# moodlight.net
KiCad netlist of a schematic drawn in EAGLE
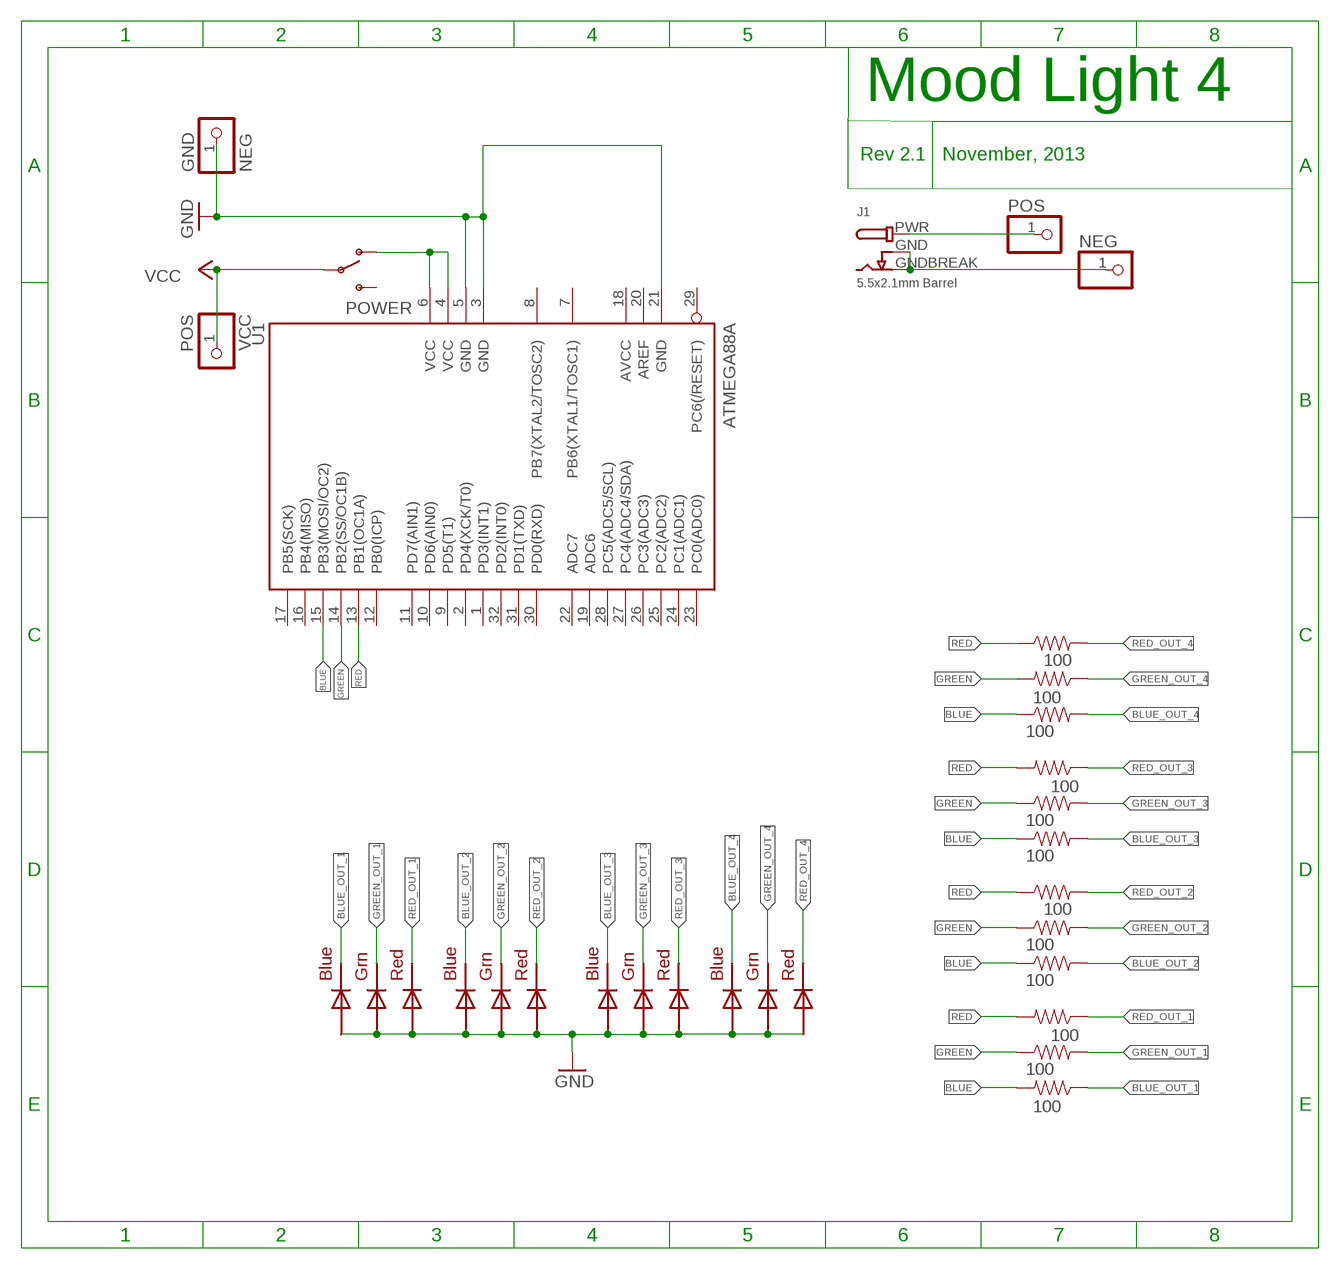
[diagram p0: schematic, sheet 1]

(export (version "E")
  (design (tool "Eeschema 10.0.6"))
  (components
    (comp (ref "GND")
      (value "NEG")
      (footprint "eagle-import:1X01")
      (libsource (lib "eagle-import") (part "PINHD-1X1"))
    )
    (comp (ref "J1")
      (value "5.5x2.1mm Barrel")
      (footprint "eagle-import:DCJACK_2MM_SMT")
      (libsource (lib "eagle-import") (part "DCBARRELSMT"))
    )
    (comp (ref "LED1")
      (value "RGBLED5050")
      (footprint "eagle-import:RGBLED5050")
      (libsource (lib "eagle-import") (part "RGBLED5050"))
    )
    (comp (ref "LED2")
      (value "RGBLED5050")
      (footprint "eagle-import:RGBLED5050")
      (libsource (lib "eagle-import") (part "RGBLED5050"))
    )
    (comp (ref "LED3")
      (value "RGBLED5050")
      (footprint "eagle-import:RGBLED5050")
      (libsource (lib "eagle-import") (part "RGBLED5050"))
    )
    (comp (ref "LED4")
      (value "RGBLED5050")
      (footprint "eagle-import:RGBLED5050")
      (libsource (lib "eagle-import") (part "RGBLED5050"))
    )
    (comp (ref "NEG")
      (value "PINHD-1X1")
      (footprint "eagle-import:1X01")
      (libsource (lib "eagle-import") (part "PINHD-1X1"))
    )
    (comp (ref "POS")
      (value "PINHD-1X1")
      (footprint "eagle-import:1X01")
      (libsource (lib "eagle-import") (part "PINHD-1X1"))
    )
    (comp (ref "POWER")
      (value "5V")
      (footprint "eagle-import:SWITCH-SPDT")
      (libsource (lib "eagle-import") (part "SWITCH-SPDTPTH"))
    )
    (comp (ref "R1")
      (value "100")
      (footprint "eagle-import:0603-RES")
      (libsource (lib "eagle-import") (part "220-5%"))
    )
    (comp (ref "R2")
      (value "100")
      (footprint "eagle-import:0603-RES")
      (libsource (lib "eagle-import") (part "220-5%"))
    )
    (comp (ref "R3")
      (value "100")
      (footprint "eagle-import:0603-RES")
      (libsource (lib "eagle-import") (part "220-5%"))
    )
    (comp (ref "R4")
      (value "100")
      (footprint "eagle-import:0603-RES")
      (libsource (lib "eagle-import") (part "220-5%"))
    )
    (comp (ref "R5")
      (value "100")
      (footprint "eagle-import:0603-RES")
      (libsource (lib "eagle-import") (part "220-5%"))
    )
    (comp (ref "R6")
      (value "100")
      (footprint "eagle-import:0603-RES")
      (libsource (lib "eagle-import") (part "220-5%"))
    )
    (comp (ref "R7")
      (value "100")
      (footprint "eagle-import:0603-RES")
      (libsource (lib "eagle-import") (part "220-5%"))
    )
    (comp (ref "R8")
      (value "100")
      (footprint "eagle-import:0603-RES")
      (libsource (lib "eagle-import") (part "220-5%"))
    )
    (comp (ref "R9")
      (value "100")
      (footprint "eagle-import:0603-RES")
      (libsource (lib "eagle-import") (part "220-5%"))
    )
    (comp (ref "R10")
      (value "100")
      (footprint "eagle-import:0603-RES")
      (libsource (lib "eagle-import") (part "220-5%"))
    )
    (comp (ref "R11")
      (value "100")
      (footprint "eagle-import:0603-RES")
      (libsource (lib "eagle-import") (part "220-5%"))
    )
    (comp (ref "R12")
      (value "100")
      (footprint "eagle-import:0603-RES")
      (libsource (lib "eagle-import") (part "220-5%"))
    )
    (comp (ref "U1")
      (value "ATMEGA88A")
      (footprint "eagle-import:TQFP32-08")
      (fields (field (name "MPN") "ATMEGA8-16AU"))
      (libsource (lib "eagle-import") (part "MEGA8-AI"))
    )
    (comp (ref "VCC")
      (value "POS")
      (footprint "eagle-import:1X01")
      (libsource (lib "eagle-import") (part "PINHD-1X1"))
    )
  )
  (nets
    (net (code "1") (name "/AVCC") (class "Default")
      (node (ref "U1") (pin "18") (pinfunction "AVCC_18") (pintype "power_in"))
    )
    (net (code "2") (name "BLUE") (class "Default")
      (node (ref "R12") (pin "2") (pinfunction "2_2") (pintype "passive"))
      (node (ref "R3") (pin "1") (pinfunction "1_1") (pintype "passive"))
      (node (ref "R6") (pin "1") (pinfunction "1_1") (pintype "passive"))
      (node (ref "R9") (pin "1") (pinfunction "1_1") (pintype "passive"))
      (node (ref "U1") (pin "15") (pinfunction "PB3(MOSI/OC2)_15") (pintype "bidirectional"))
    )
    (net (code "3") (name "BLUE_OUT_1") (class "Default")
      (node (ref "LED1") (pin "4") (pinfunction "BLUE_C_4") (pintype "bidirectional"))
      (node (ref "R12") (pin "1") (pinfunction "1_1") (pintype "passive"))
    )
    (net (code "4") (name "BLUE_OUT_2") (class "Default")
      (node (ref "LED2") (pin "4") (pinfunction "BLUE_C_4") (pintype "bidirectional"))
      (node (ref "R9") (pin "2") (pinfunction "2_2") (pintype "passive"))
    )
    (net (code "5") (name "BLUE_OUT_3") (class "Default")
      (node (ref "LED3") (pin "4") (pinfunction "BLUE_C_4") (pintype "bidirectional"))
      (node (ref "R6") (pin "2") (pinfunction "2_2") (pintype "passive"))
    )
    (net (code "6") (name "BLUE_OUT_4") (class "Default")
      (node (ref "LED4") (pin "4") (pinfunction "BLUE_C_4") (pintype "bidirectional"))
      (node (ref "R3") (pin "2") (pinfunction "2_2") (pintype "passive"))
    )
    (net (code "7") (name "GND") (class "Default")
      (node (ref "GND") (pin "1") (pinfunction "1_1") (pintype "passive"))
      (node (ref "LED1") (pin "1") (pinfunction "GREEN_A_1") (pintype "bidirectional"))
      (node (ref "LED1") (pin "2") (pinfunction "RED_A_2") (pintype "bidirectional"))
      (node (ref "LED1") (pin "3") (pinfunction "BLUE_A_3") (pintype "bidirectional"))
      (node (ref "LED2") (pin "1") (pinfunction "GREEN_A_1") (pintype "bidirectional"))
      (node (ref "LED2") (pin "2") (pinfunction "RED_A_2") (pintype "bidirectional"))
      (node (ref "LED2") (pin "3") (pinfunction "BLUE_A_3") (pintype "bidirectional"))
      (node (ref "LED3") (pin "1") (pinfunction "GREEN_A_1") (pintype "bidirectional"))
      (node (ref "LED3") (pin "2") (pinfunction "RED_A_2") (pintype "bidirectional"))
      (node (ref "LED3") (pin "3") (pinfunction "BLUE_A_3") (pintype "bidirectional"))
      (node (ref "LED4") (pin "1") (pinfunction "GREEN_A_1") (pintype "bidirectional"))
      (node (ref "LED4") (pin "2") (pinfunction "RED_A_2") (pintype "bidirectional"))
      (node (ref "LED4") (pin "3") (pinfunction "BLUE_A_3") (pintype "bidirectional"))
      (node (ref "U1") (pin "21") (pinfunction "GND_21") (pintype "power_in"))
      (node (ref "U1") (pin "3") (pinfunction "GND_3") (pintype "power_in"))
      (node (ref "U1") (pin "5") (pinfunction "GND_5") (pintype "power_in"))
    )
    (net (code "8") (name "GREEN") (class "Default")
      (node (ref "R11") (pin "1") (pinfunction "1_1") (pintype "passive"))
      (node (ref "R2") (pin "2") (pinfunction "2_2") (pintype "passive"))
      (node (ref "R5") (pin "1") (pinfunction "1_1") (pintype "passive"))
      (node (ref "R8") (pin "1") (pinfunction "1_1") (pintype "passive"))
      (node (ref "U1") (pin "14") (pinfunction "PB2(SS/OC1B)_14") (pintype "bidirectional"))
    )
    (net (code "9") (name "GREEN_OUT_1") (class "Default")
      (node (ref "LED1") (pin "6") (pinfunction "GREEN_C_6") (pintype "bidirectional"))
      (node (ref "R11") (pin "2") (pinfunction "2_2") (pintype "passive"))
    )
    (net (code "10") (name "GREEN_OUT_2") (class "Default")
      (node (ref "LED2") (pin "6") (pinfunction "GREEN_C_6") (pintype "bidirectional"))
      (node (ref "R8") (pin "2") (pinfunction "2_2") (pintype "passive"))
    )
    (net (code "11") (name "GREEN_OUT_3") (class "Default")
      (node (ref "LED3") (pin "6") (pinfunction "GREEN_C_6") (pintype "bidirectional"))
      (node (ref "R5") (pin "2") (pinfunction "2_2") (pintype "passive"))
    )
    (net (code "12") (name "GREEN_OUT_4") (class "Default")
      (node (ref "LED4") (pin "6") (pinfunction "GREEN_C_6") (pintype "bidirectional"))
      (node (ref "R2") (pin "1") (pinfunction "1_1") (pintype "passive"))
    )
    (net (code "13") (name "Net-(J1-GND)") (class "Default")
      (node (ref "J1") (pin "GND") (pinfunction "GNDBREAK_GND") (pintype "power_in"))
      (node (ref "J1") (pin "GNDBREAK") (pinfunction "GND_GNDBREAK") (pintype "power_in"))
      (node (ref "NEG") (pin "1") (pinfunction "1_1") (pintype "passive"))
    )
    (net (code "14") (name "Net-(J1-PadPWR)") (class "Default")
      (node (ref "J1") (pin "PWR") (pinfunction "PWR_PWR") (pintype "power_in"))
      (node (ref "POS") (pin "1") (pinfunction "1_1") (pintype "passive"))
    )
    (net (code "15") (name "Net-(POWER-O)") (class "Default")
      (node (ref "POWER") (pin "1") (pinfunction "O_1") (pintype "passive"))
      (node (ref "U1") (pin "4") (pinfunction "VCC_4") (pintype "power_in"))
      (node (ref "U1") (pin "6") (pinfunction "VCC_6") (pintype "power_in"))
    )
    (net (code "16") (name "RED") (class "Default")
      (node (ref "R1") (pin "1") (pinfunction "1_1") (pintype "passive"))
      (node (ref "R10") (pin "2") (pinfunction "2_2") (pintype "passive"))
      (node (ref "R4") (pin "2") (pinfunction "2_2") (pintype "passive"))
      (node (ref "R7") (pin "1") (pinfunction "1_1") (pintype "passive"))
      (node (ref "U1") (pin "13") (pinfunction "PB1(OC1A)_13") (pintype "bidirectional"))
    )
    (net (code "17") (name "RED_OUT_1") (class "Default")
      (node (ref "LED1") (pin "5") (pinfunction "RED_C_5") (pintype "bidirectional"))
      (node (ref "R10") (pin "1") (pinfunction "1_1") (pintype "passive"))
    )
    (net (code "18") (name "RED_OUT_2") (class "Default")
      (node (ref "LED2") (pin "5") (pinfunction "RED_C_5") (pintype "bidirectional"))
      (node (ref "R7") (pin "2") (pinfunction "2_2") (pintype "passive"))
    )
    (net (code "19") (name "RED_OUT_3") (class "Default")
      (node (ref "LED3") (pin "5") (pinfunction "RED_C_5") (pintype "bidirectional"))
      (node (ref "R4") (pin "1") (pinfunction "1_1") (pintype "passive"))
    )
    (net (code "20") (name "RED_OUT_4") (class "Default")
      (node (ref "LED4") (pin "5") (pinfunction "RED_C_5") (pintype "bidirectional"))
      (node (ref "R1") (pin "2") (pinfunction "2_2") (pintype "passive"))
    )
    (net (code "21") (name "VCC") (class "Default")
      (node (ref "POWER") (pin "2") (pinfunction "P_2") (pintype "passive"))
      (node (ref "VCC") (pin "1") (pinfunction "1_1") (pintype "passive"))
    )
    (net (code "22") (name "unconnected-(POWER-S-Pad3)") (class "Default")
      (node (ref "POWER") (pin "3") (pinfunction "S_3") (pintype "passive"))
    )
    (net (code "23") (name "unconnected-(U1-ADC6-Pad19)") (class "Default")
      (node (ref "U1") (pin "19") (pinfunction "ADC6_19") (pintype "bidirectional"))
    )
    (net (code "24") (name "unconnected-(U1-ADC7-Pad22)") (class "Default")
      (node (ref "U1") (pin "22") (pinfunction "ADC7_22") (pintype "bidirectional"))
    )
    (net (code "25") (name "unconnected-(U1-AREF-Pad20)") (class "Default")
      (node (ref "U1") (pin "20") (pinfunction "AREF_20") (pintype "passive"))
    )
    (net (code "26") (name "unconnected-(U1-PB0(ICP)-Pad12)") (class "Default")
      (node (ref "U1") (pin "12") (pinfunction "PB0(ICP)_12") (pintype "bidirectional"))
    )
    (net (code "27") (name "unconnected-(U1-PB4(MISO)-Pad16)") (class "Default")
      (node (ref "U1") (pin "16") (pinfunction "PB4(MISO)_16") (pintype "bidirectional"))
    )
    (net (code "28") (name "unconnected-(U1-PB5(SCK)-Pad17)") (class "Default")
      (node (ref "U1") (pin "17") (pinfunction "PB5(SCK)_17") (pintype "bidirectional"))
    )
    (net (code "29") (name "unconnected-(U1-PB6(XTAL1{slash}TOSC1)-Pad7)") (class "Default")
      (node (ref "U1") (pin "7") (pinfunction "PB6(XTAL1/TOSC1)_7") (pintype "bidirectional"))
    )
    (net (code "30") (name "unconnected-(U1-PB7(XTAL2{slash}TOSC2)-Pad8)") (class "Default")
      (node (ref "U1") (pin "8") (pinfunction "PB7(XTAL2/TOSC2)_8") (pintype "bidirectional"))
    )
    (net (code "31") (name "unconnected-(U1-PC0(ADC0)-Pad23)") (class "Default")
      (node (ref "U1") (pin "23") (pinfunction "PC0(ADC0)_23") (pintype "bidirectional"))
    )
    (net (code "32") (name "unconnected-(U1-PC1(ADC1)-Pad24)") (class "Default")
      (node (ref "U1") (pin "24") (pinfunction "PC1(ADC1)_24") (pintype "bidirectional"))
    )
    (net (code "33") (name "unconnected-(U1-PC2(ADC2)-Pad25)") (class "Default")
      (node (ref "U1") (pin "25") (pinfunction "PC2(ADC2)_25") (pintype "bidirectional"))
    )
    (net (code "34") (name "unconnected-(U1-PC3(ADC3)-Pad26)") (class "Default")
      (node (ref "U1") (pin "26") (pinfunction "PC3(ADC3)_26") (pintype "bidirectional"))
    )
    (net (code "35") (name "unconnected-(U1-PC4(ADC4{slash}SDA)-Pad27)") (class "Default")
      (node (ref "U1") (pin "27") (pinfunction "PC4(ADC4/SDA)_27") (pintype "bidirectional"))
    )
    (net (code "36") (name "unconnected-(U1-PC5(ADC5{slash}SCL)-Pad28)") (class "Default")
      (node (ref "U1") (pin "28") (pinfunction "PC5(ADC5/SCL)_28") (pintype "bidirectional"))
    )
    (net (code "37") (name "unconnected-(U1-PC6({slash}RESET)-Pad29)") (class "Default")
      (node (ref "U1") (pin "29") (pinfunction "PC6(/RESET)_29") (pintype "bidirectional"))
    )
    (net (code "38") (name "unconnected-(U1-PD0(RXD)-Pad30)") (class "Default")
      (node (ref "U1") (pin "30") (pinfunction "PD0(RXD)_30") (pintype "bidirectional"))
    )
    (net (code "39") (name "unconnected-(U1-PD1(TXD)-Pad31)") (class "Default")
      (node (ref "U1") (pin "31") (pinfunction "PD1(TXD)_31") (pintype "bidirectional"))
    )
    (net (code "40") (name "unconnected-(U1-PD2(INT0)-Pad32)") (class "Default")
      (node (ref "U1") (pin "32") (pinfunction "PD2(INT0)_32") (pintype "bidirectional"))
    )
    (net (code "41") (name "unconnected-(U1-PD3(INT1)-Pad1)") (class "Default")
      (node (ref "U1") (pin "1") (pinfunction "PD3(INT1)_1") (pintype "bidirectional"))
    )
    (net (code "42") (name "unconnected-(U1-PD4(XCK{slash}T0)-Pad2)") (class "Default")
      (node (ref "U1") (pin "2") (pinfunction "PD4(XCK/T0)_2") (pintype "bidirectional"))
    )
    (net (code "43") (name "unconnected-(U1-PD5(T1)-Pad9)") (class "Default")
      (node (ref "U1") (pin "9") (pinfunction "PD5(T1)_9") (pintype "bidirectional"))
    )
    (net (code "44") (name "unconnected-(U1-PD6(AIN0)-Pad10)") (class "Default")
      (node (ref "U1") (pin "10") (pinfunction "PD6(AIN0)_10") (pintype "bidirectional"))
    )
    (net (code "45") (name "unconnected-(U1-PD7(AIN1)-Pad11)") (class "Default")
      (node (ref "U1") (pin "11") (pinfunction "PD7(AIN1)_11") (pintype "bidirectional"))
    )
  )
)
